# Current_measurement_circuit.net
KiCad netlist of a schematic drawn in Altium Designer
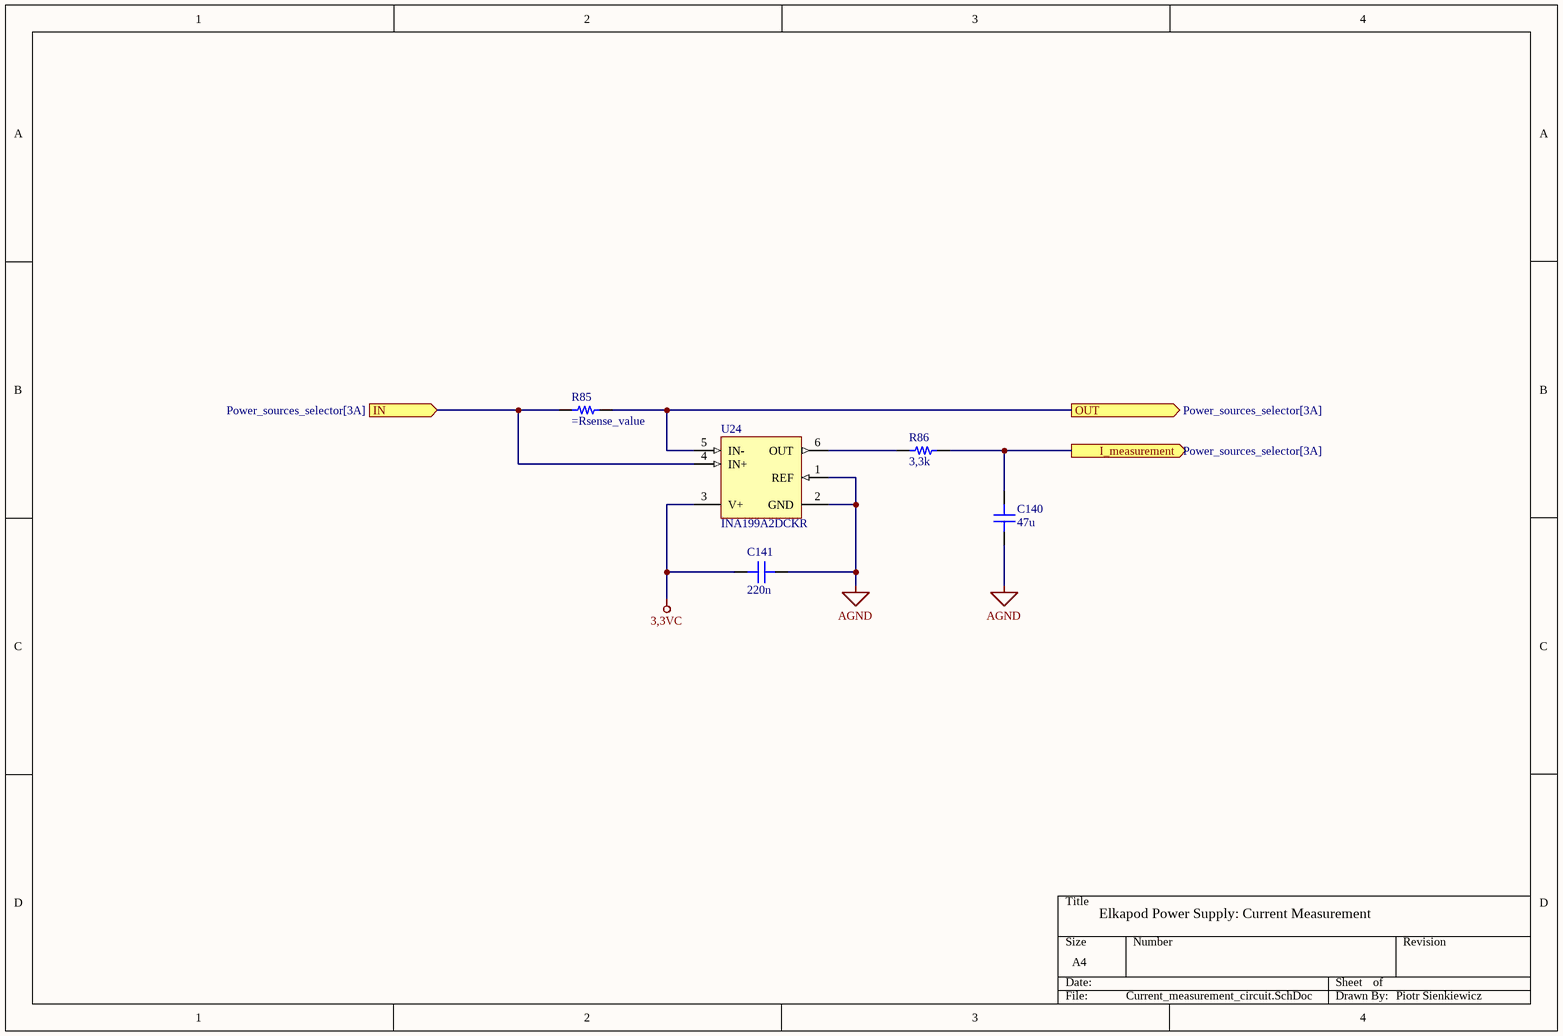
[diagram p0: Current_measurement_circuit.SchDoc]

(export (version "E")
  (design (tool "Eeschema 10.0.6"))
  (components
    (comp (ref "C140")
      (value "47u")
      (footprint "CAP 0603_1608")
      (description "CAP CER 47uF 6,3V X5R 0603")
      (fields (field (name "PART NUMBER") "C0603C272F3GAC7867") (field (name "MANUFACTURER") "KEMET"))
      (libsource (lib "Celestial Altium Library - altium_library") (part "Capacitor"))
    )
    (comp (ref "C141")
      (value "220n")
      (footprint "CAP 0603_1608")
      (description "CAP CER 220nF 25V X5R 0603")
      (fields (field (name "PART NUMBER") "C0603C272F3GAC7867") (field (name "MANUFACTURER") "KEMET"))
      (libsource (lib "Celestial Altium Library - altium_library") (part "Capacitor"))
    )
    (comp (ref "R85")
      (value "~")
      (footprint "STACKPOLE CSM2512")
      (description "RES 1% 3W 2512")
      (fields
        (field (name "PART NUMBER") "CSM2512FT20L0")
        (field (name "MANUFACTURER") "Stackpole Electronics Inc")
      )
      (libsource (lib "Celestial Altium Library - altium_library") (part "Resistor"))
    )
    (comp (ref "R86")
      (value "3,3k")
      (footprint "RES 0603_1608")
      (description "RES 3,3K OHM 1% 0,1W 0603")
      (fields
        (field (name "PART NUMBER") "RNCS0603BKE10K0")
        (field (name "MANUFACTURER") "Stackpole Electronics Inc")
      )
      (libsource (lib "Celestial Altium Library - altium_library") (part "Resistor"))
    )
    (comp (ref "U24")
      (value "INA199A2DCKR")
      (footprint "DCK0006A_N")
      (libsource (lib "Altium Content Vault") (part "TI-INA199A2DCK6"))
    )
  )
  (nets
    (net (code "1") (name "/IN") (class "Default")
      (node (ref "R85") (pin "2") (pinfunction "2_2") (pintype "passive"))
      (node (ref "U24") (pin "4") (pinfunction "IN+_4") (pintype "input"))
    )
    (net (code "2") (name "/I_measurement") (class "Default")
      (node (ref "C140") (pin "2") (pinfunction "2_2") (pintype "passive"))
      (node (ref "R86") (pin "2") (pinfunction "2_2") (pintype "passive"))
    )
    (net (code "3") (name "/OUT") (class "Default")
      (node (ref "R85") (pin "1") (pinfunction "1_1") (pintype "passive"))
      (node (ref "U24") (pin "5") (pinfunction "IN-_5") (pintype "input"))
    )
    (net (code "4") (name "3,3VC") (class "Default")
      (node (ref "C141") (pin "2") (pinfunction "2_2") (pintype "passive"))
      (node (ref "U24") (pin "3") (pinfunction "V+_3") (pintype "power_in"))
    )
    (net (code "5") (name "AGND") (class "Default")
      (node (ref "C140") (pin "1") (pinfunction "1_1") (pintype "passive"))
      (node (ref "C141") (pin "1") (pinfunction "1_1") (pintype "passive"))
      (node (ref "U24") (pin "1") (pinfunction "REF_1") (pintype "input"))
      (node (ref "U24") (pin "2") (pinfunction "GND_2") (pintype "power_in"))
    )
    (net (code "6") (name "Net-(U24-OUT)") (class "Default")
      (node (ref "R86") (pin "1") (pinfunction "1_1") (pintype "passive"))
      (node (ref "U24") (pin "6") (pinfunction "OUT_6") (pintype "output"))
    )
  )
)
